# Sheet1.net
KiCad netlist of a schematic drawn in Altium Designer
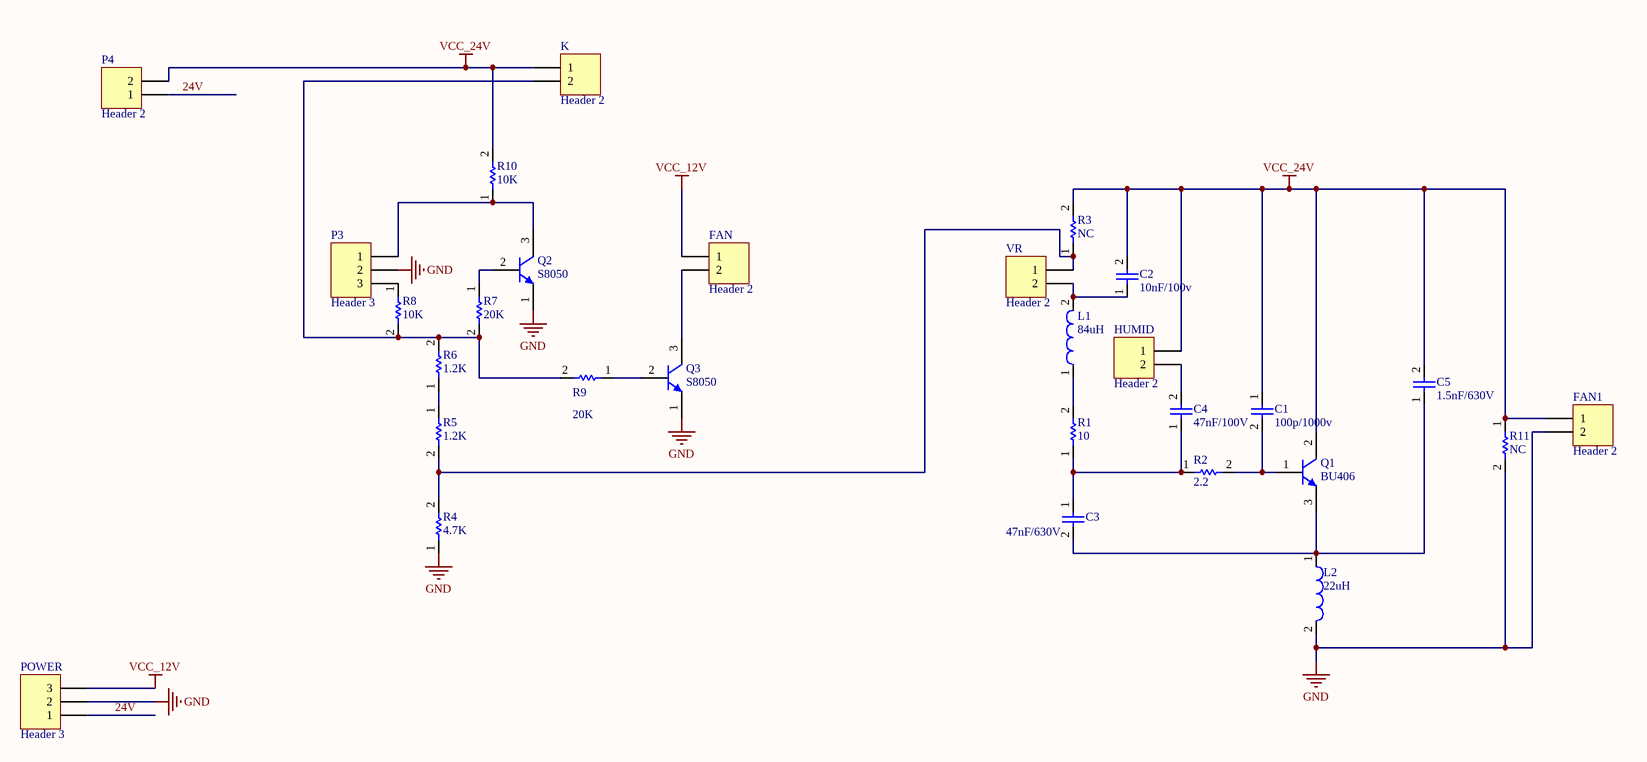
[diagram p0: Sheet1.SchDoc]

(export (version "E")
  (design (tool "Eeschema 10.0.6"))
  (components
    (comp (ref "C1")
      (value "100p/1000v")
      (footprint "CAP_5MM")
      (description "Capacitor")
      (fields (field (name "PUBLISHER") "Altium Limited"))
      (libsource (lib "Miscellaneous Devices") (part "Cap"))
    )
    (comp (ref "C2")
      (value "10nF/100v")
      (footprint "CAP_5MM")
      (description "Capacitor")
      (fields (field (name "PUBLISHER") "Altium Limited"))
      (libsource (lib "Miscellaneous Devices") (part "Cap"))
    )
    (comp (ref "C3")
      (value "47nF/630V")
      (footprint "AXIAL-0.4")
      (description "Capacitor")
      (fields (field (name "PUBLISHER") "Altium Limited"))
      (libsource (lib "Miscellaneous Devices") (part "Cap"))
    )
    (comp (ref "C4")
      (value "47nF/100V")
      (footprint "AXIAL-0.4")
      (description "Capacitor")
      (fields (field (name "PUBLISHER") "Altium Limited"))
      (libsource (lib "Miscellaneous Devices") (part "Cap"))
    )
    (comp (ref "C5")
      (value "1.5nF/630V")
      (footprint "AXIAL-0.3")
      (description "Capacitor")
      (fields (field (name "PUBLISHER") "Altium Limited"))
      (libsource (lib "Miscellaneous Devices") (part "Cap"))
    )
    (comp (ref "FAN")
      (value "Header 2")
      (footprint "SIP-2L")
      (description "Header, 2-Pin")
      (fields (field (name "PUBLISHER") "Altium Limited"))
      (libsource (lib "Miscellaneous Connectors") (part "Header 2"))
    )
    (comp (ref "FAN1")
      (value "Header 2")
      (footprint "SIP-2L")
      (description "Header, 2-Pin")
      (fields (field (name "PUBLISHER") "Altium Limited"))
      (libsource (lib "Miscellaneous Connectors") (part "Header 2"))
    )
    (comp (ref "HUMID")
      (value "Header 2")
      (footprint "SIP-2L")
      (description "Header, 2-Pin")
      (fields (field (name "PUBLISHER") "Altium Limited"))
      (libsource (lib "") (part "Header 2_2"))
    )
    (comp (ref "K")
      (value "Header 2")
      (footprint "SIP-2L")
      (description "Header, 2-Pin")
      (fields (field (name "PUBLISHER") "Altium Limited"))
      (libsource (lib "Miscellaneous Connectors") (part "Header 2"))
    )
    (comp (ref "L1")
      (value "84uH")
      (footprint "AXIAL-0.5")
      (description "Inductor")
      (fields (field (name "PUBLISHER") "Altium Limited"))
      (libsource (lib "Miscellaneous Devices") (part "Inductor"))
    )
    (comp (ref "L2")
      (value "22uH")
      (footprint "6*8")
      (description "Inductor")
      (fields (field (name "PUBLISHER") "Altium Limited"))
      (libsource (lib "Miscellaneous Devices") (part "Inductor"))
    )
    (comp (ref "P3")
      (value "Header 3")
      (footprint "SIP-3L")
      (description "Header, 3-Pin")
      (fields (field (name "PUBLISHER") "Altium Limited"))
      (libsource (lib "Miscellaneous Connectors") (part "Header 3"))
    )
    (comp (ref "P4")
      (value "Header 2")
      (footprint "SIP-2L")
      (description "Header, 2-Pin")
      (fields (field (name "PUBLISHER") "Altium Limited"))
      (libsource (lib "") (part "Header 2_1"))
    )
    (comp (ref "POWER")
      (value "Header 3")
      (footprint "SIP-3L")
      (description "Header, 3-Pin")
      (fields (field (name "PUBLISHER") "Altium Limited"))
      (libsource (lib "") (part "Header 3_1"))
    )
    (comp (ref "Q1")
      (value "BU406")
      (footprint "to220")
      (description "NPN Bipolar Transistor")
      (fields (field (name "PUBLISHER") "Altium Limited"))
      (libsource (lib "Miscellaneous Devices") (part "NPN"))
    )
    (comp (ref "Q2")
      (value "S8050")
      (footprint "to-92")
      (description "NPN Bipolar Transistor")
      (fields (field (name "PUBLISHER") "Altium Limited"))
      (libsource (lib "") (part "NPN_1"))
    )
    (comp (ref "Q3")
      (value "S8050")
      (footprint "to-92")
      (description "NPN Bipolar Transistor")
      (fields (field (name "PUBLISHER") "Altium Limited"))
      (libsource (lib "") (part "NPN_1"))
    )
    (comp (ref "R1")
      (value "10")
      (footprint "AXIAL-0.4")
      (description "Semiconductor Resistor")
      (fields (field (name "PUBLISHER") "Altium Limited"))
      (libsource (lib "Miscellaneous Devices") (part "Res Semi"))
    )
    (comp (ref "R2")
      (value "2.2")
      (footprint "AXIAL-0.4")
      (description "Semiconductor Resistor")
      (fields (field (name "PUBLISHER") "Altium Limited"))
      (libsource (lib "Miscellaneous Devices") (part "Res Semi"))
    )
    (comp (ref "R3")
      (value "NC")
      (footprint "AXIAL-0.3")
      (description "Semiconductor Resistor")
      (fields (field (name "PUBLISHER") "Altium Limited"))
      (libsource (lib "Miscellaneous Devices") (part "Res Semi"))
    )
    (comp (ref "R4")
      (value "4.7K")
      (footprint "AXIAL-0.4")
      (description "Semiconductor Resistor")
      (fields (field (name "PUBLISHER") "Altium Limited"))
      (libsource (lib "Miscellaneous Devices") (part "Res Semi"))
    )
    (comp (ref "R5")
      (value "1.2K")
      (footprint "AXIAL-0.4")
      (description "Semiconductor Resistor")
      (fields (field (name "PUBLISHER") "Altium Limited"))
      (libsource (lib "Miscellaneous Devices") (part "Res Semi"))
    )
    (comp (ref "R6")
      (value "1.2K")
      (footprint "AXIAL-0.4")
      (description "Semiconductor Resistor")
      (fields (field (name "PUBLISHER") "Altium Limited"))
      (libsource (lib "Miscellaneous Devices") (part "Res Semi"))
    )
    (comp (ref "R7")
      (value "20K")
      (footprint "AXIAL-0.4")
      (description "Semiconductor Resistor")
      (fields (field (name "PUBLISHER") "Altium Limited"))
      (libsource (lib "Miscellaneous Devices") (part "Res Semi"))
    )
    (comp (ref "R8")
      (value "10K")
      (footprint "AXIAL-0.4")
      (description "Semiconductor Resistor")
      (fields (field (name "PUBLISHER") "Altium Limited"))
      (libsource (lib "Miscellaneous Devices") (part "Res Semi"))
    )
    (comp (ref "R9")
      (value "20K")
      (footprint "AXIAL-0.4")
      (description "Semiconductor Resistor")
      (fields (field (name "PUBLISHER") "Altium Limited"))
      (libsource (lib "Miscellaneous Devices") (part "Res Semi"))
    )
    (comp (ref "R10")
      (value "10K")
      (footprint "AXIAL-0.4")
      (description "Semiconductor Resistor")
      (fields (field (name "PUBLISHER") "Altium Limited"))
      (libsource (lib "Miscellaneous Devices") (part "Res Semi"))
    )
    (comp (ref "R11")
      (value "NC")
      (footprint "AXIAL-0.4")
      (description "Semiconductor Resistor")
      (fields (field (name "PUBLISHER") "Altium Limited"))
      (libsource (lib "Miscellaneous Devices") (part "Res Semi"))
    )
    (comp (ref "VR")
      (value "Header 2")
      (footprint "SIP-2L")
      (description "Header, 2-Pin")
      (fields (field (name "PUBLISHER") "Altium Limited"))
      (libsource (lib "") (part "Header 2_2"))
    )
  )
  (nets
    (net (code "1") (name "/24V") (class "Default")
      (node (ref "P4") (pin "1") (pinfunction "1_1") (pintype "passive"))
      (node (ref "POWER") (pin "1") (pinfunction "1_1") (pintype "passive"))
    )
    (net (code "2") (name "GND") (class "Default")
      (node (ref "FAN1") (pin "2") (pinfunction "2_2") (pintype "passive"))
      (node (ref "L2") (pin "2") (pinfunction "2_2") (pintype "passive"))
      (node (ref "P3") (pin "2") (pinfunction "2_2") (pintype "passive"))
      (node (ref "POWER") (pin "2") (pinfunction "2_2") (pintype "passive"))
      (node (ref "Q2") (pin "1") (pinfunction "E_1") (pintype "passive"))
      (node (ref "Q3") (pin "1") (pinfunction "E_1") (pintype "passive"))
      (node (ref "R11") (pin "2") (pinfunction "2_2") (pintype "passive"))
      (node (ref "R4") (pin "1") (pinfunction "1_1") (pintype "passive"))
    )
    (net (code "3") (name "Net-(C2-Pad1)") (class "Default")
      (node (ref "C2") (pin "1") (pinfunction "1_1") (pintype "passive"))
      (node (ref "L1") (pin "2") (pinfunction "2_2") (pintype "passive"))
      (node (ref "VR") (pin "2") (pinfunction "2_2") (pintype "passive"))
    )
    (net (code "4") (name "Net-(C3-Pad1)") (class "Default")
      (node (ref "C3") (pin "1") (pinfunction "1_1") (pintype "passive"))
      (node (ref "C4") (pin "1") (pinfunction "1_1") (pintype "passive"))
      (node (ref "R1") (pin "1") (pinfunction "1_1") (pintype "passive"))
      (node (ref "R2") (pin "1") (pinfunction "1_1") (pintype "passive"))
    )
    (net (code "5") (name "Net-(C4-Pad2)") (class "Default")
      (node (ref "C4") (pin "2") (pinfunction "2_2") (pintype "passive"))
      (node (ref "HUMID") (pin "2") (pinfunction "2_2") (pintype "passive"))
    )
    (net (code "6") (name "Net-(K-Pad2)") (class "Default")
      (node (ref "K") (pin "2") (pinfunction "2_2") (pintype "passive"))
      (node (ref "R6") (pin "2") (pinfunction "2_2") (pintype "passive"))
      (node (ref "R7") (pin "2") (pinfunction "2_2") (pintype "passive"))
      (node (ref "R8") (pin "2") (pinfunction "2_2") (pintype "passive"))
      (node (ref "R9") (pin "2") (pinfunction "2_2") (pintype "passive"))
    )
    (net (code "7") (name "Net-(L1-Pad1)") (class "Default")
      (node (ref "L1") (pin "1") (pinfunction "1_1") (pintype "passive"))
      (node (ref "R1") (pin "2") (pinfunction "2_2") (pintype "passive"))
    )
    (net (code "8") (name "Net-(P3-Pad3)") (class "Default")
      (node (ref "P3") (pin "3") (pinfunction "3_3") (pintype "passive"))
      (node (ref "R8") (pin "1") (pinfunction "1_1") (pintype "passive"))
    )
    (net (code "9") (name "Net-(Q1-B)") (class "Default")
      (node (ref "C1") (pin "2") (pinfunction "2_2") (pintype "passive"))
      (node (ref "Q1") (pin "1") (pinfunction "B_1") (pintype "passive"))
      (node (ref "R2") (pin "2") (pinfunction "2_2") (pintype "passive"))
    )
    (net (code "10") (name "Net-(Q1-E)") (class "Default")
      (node (ref "C3") (pin "2") (pinfunction "2_2") (pintype "passive"))
      (node (ref "C5") (pin "1") (pinfunction "1_1") (pintype "passive"))
      (node (ref "L2") (pin "1") (pinfunction "1_1") (pintype "passive"))
      (node (ref "Q1") (pin "3") (pinfunction "E_3") (pintype "passive"))
    )
    (net (code "11") (name "Net-(Q2-B)") (class "Default")
      (node (ref "Q2") (pin "2") (pinfunction "B_2") (pintype "passive"))
      (node (ref "R7") (pin "1") (pinfunction "1_1") (pintype "passive"))
    )
    (net (code "12") (name "Net-(Q2-C)") (class "Default")
      (node (ref "P3") (pin "1") (pinfunction "1_1") (pintype "passive"))
      (node (ref "Q2") (pin "3") (pinfunction "C_3") (pintype "passive"))
      (node (ref "R10") (pin "1") (pinfunction "1_1") (pintype "passive"))
    )
    (net (code "13") (name "Net-(Q3-B)") (class "Default")
      (node (ref "Q3") (pin "2") (pinfunction "B_2") (pintype "passive"))
      (node (ref "R9") (pin "1") (pinfunction "1_1") (pintype "passive"))
    )
    (net (code "14") (name "Net-(Q3-C)") (class "Default")
      (node (ref "FAN") (pin "2") (pinfunction "2_2") (pintype "passive"))
      (node (ref "Q3") (pin "3") (pinfunction "C_3") (pintype "passive"))
    )
    (net (code "15") (name "Net-(R3-Pad1)") (class "Default")
      (node (ref "R3") (pin "1") (pinfunction "1_1") (pintype "passive"))
      (node (ref "R4") (pin "2") (pinfunction "2_2") (pintype "passive"))
      (node (ref "R5") (pin "2") (pinfunction "2_2") (pintype "passive"))
      (node (ref "VR") (pin "1") (pinfunction "1_1") (pintype "passive"))
    )
    (net (code "16") (name "Net-(R5-Pad1)") (class "Default")
      (node (ref "R5") (pin "1") (pinfunction "1_1") (pintype "passive"))
      (node (ref "R6") (pin "1") (pinfunction "1_1") (pintype "passive"))
    )
    (net (code "17") (name "VCC_12V") (class "Default")
      (node (ref "FAN") (pin "1") (pinfunction "1_1") (pintype "passive"))
      (node (ref "POWER") (pin "3") (pinfunction "3_3") (pintype "passive"))
    )
    (net (code "18") (name "VCC_24V") (class "Default")
      (node (ref "C1") (pin "1") (pinfunction "1_1") (pintype "passive"))
      (node (ref "C2") (pin "2") (pinfunction "2_2") (pintype "passive"))
      (node (ref "C5") (pin "2") (pinfunction "2_2") (pintype "passive"))
      (node (ref "FAN1") (pin "1") (pinfunction "1_1") (pintype "passive"))
      (node (ref "HUMID") (pin "1") (pinfunction "1_1") (pintype "passive"))
      (node (ref "K") (pin "1") (pinfunction "1_1") (pintype "passive"))
      (node (ref "P4") (pin "2") (pinfunction "2_2") (pintype "passive"))
      (node (ref "Q1") (pin "2") (pinfunction "C_2") (pintype "passive"))
      (node (ref "R10") (pin "2") (pinfunction "2_2") (pintype "passive"))
      (node (ref "R11") (pin "1") (pinfunction "1_1") (pintype "passive"))
      (node (ref "R3") (pin "2") (pinfunction "2_2") (pintype "passive"))
    )
  )
)
